# ST-Link_V2_Dongle.net
KiCad netlist of a schematic drawn in Altium Designer
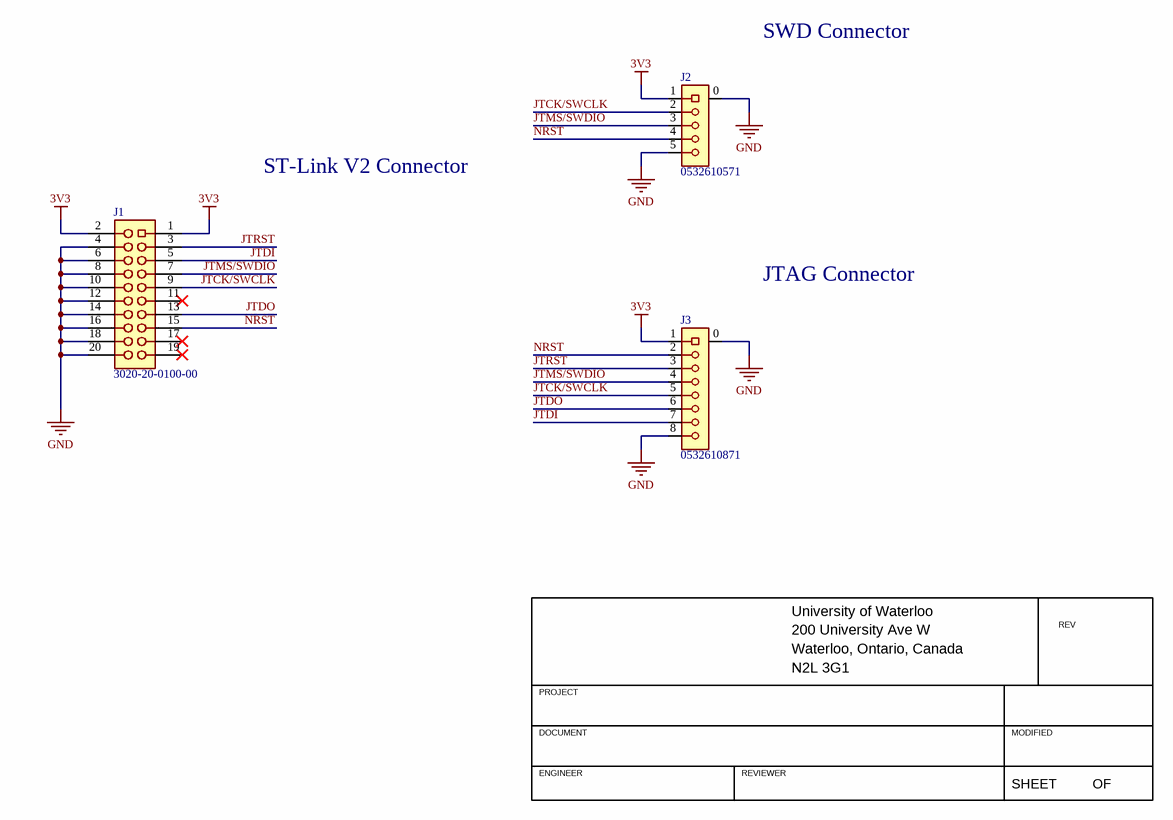
[diagram p0: ST-Link V2 Dongle.SchDoc]

(export (version "E")
  (design (tool "Eeschema 10.0.6"))
  (components
    (comp (ref "J1")
      (value "3020-20-0100-00")
      (footprint "CNC_3020-20-0100-00")
      (description "CONN HEADER VERT 20POS 2.54MM")
      (libsource (lib "Personal_Schematic_Library_2022") (part "CON_10x2_HEADER"))
    )
    (comp (ref "J2")
      (value "CON_MOLEX-PICO_5POS_RA")
      (footprint "MOLEX-532610571")
      (description "CONN HEADER SMD R/A 5POS 1.25MM")
      (fields (field (name "MANUFACTURER PART NUMBER 1") "0532610571"))
      (libsource (lib "Personal_Schematic_Library_2022") (part "CON_MOLEX-PICO_5POS_RA"))
    )
    (comp (ref "J3")
      (value "CON_MOLEX-PICO_8POS_RA")
      (footprint "MOLEX-532610871")
      (description "CONN HEADER SMD R/A 8POS 1.25MM")
      (fields (field (name "MANUFACTURER PART NUMBER 1") "0532610871"))
      (libsource (lib "Personal_Schematic_Library_2022") (part "CON_MOLEX-PICO_8POS_RA"))
    )
  )
  (nets
    (net (code "1") (name "/JTCK{slash}SWCLK") (class "Default")
      (node (ref "J1") (pin "9") (pinfunction "9_9") (pintype "passive"))
      (node (ref "J2") (pin "2") (pinfunction "2_2") (pintype "passive"))
      (node (ref "J3") (pin "5") (pinfunction "5_5") (pintype "passive"))
    )
    (net (code "2") (name "/JTDI") (class "Default")
      (node (ref "J1") (pin "5") (pinfunction "5_5") (pintype "passive"))
      (node (ref "J3") (pin "7") (pinfunction "7_7") (pintype "passive"))
    )
    (net (code "3") (name "/JTDO") (class "Default")
      (node (ref "J1") (pin "13") (pinfunction "13_13") (pintype "passive"))
      (node (ref "J3") (pin "6") (pinfunction "6_6") (pintype "passive"))
    )
    (net (code "4") (name "/JTMS{slash}SWDIO") (class "Default")
      (node (ref "J1") (pin "7") (pinfunction "7_7") (pintype "passive"))
      (node (ref "J2") (pin "3") (pinfunction "3_3") (pintype "passive"))
      (node (ref "J3") (pin "4") (pinfunction "4_4") (pintype "passive"))
    )
    (net (code "5") (name "/JTRST") (class "Default")
      (node (ref "J1") (pin "3") (pinfunction "3_3") (pintype "passive"))
      (node (ref "J3") (pin "3") (pinfunction "3_3") (pintype "passive"))
    )
    (net (code "6") (name "/NRST") (class "Default")
      (node (ref "J1") (pin "15") (pinfunction "15_15") (pintype "passive"))
      (node (ref "J2") (pin "4") (pinfunction "4_4") (pintype "passive"))
      (node (ref "J3") (pin "2") (pinfunction "2_2") (pintype "passive"))
    )
    (net (code "7") (name "3V3") (class "Default")
      (node (ref "J1") (pin "1") (pinfunction "1_1") (pintype "passive"))
      (node (ref "J1") (pin "2") (pinfunction "2_2") (pintype "passive"))
      (node (ref "J2") (pin "1") (pinfunction "1_1") (pintype "passive"))
      (node (ref "J3") (pin "1") (pinfunction "1_1") (pintype "passive"))
    )
    (net (code "8") (name "GND") (class "Default")
      (node (ref "J1") (pin "10") (pinfunction "10_10") (pintype "passive"))
      (node (ref "J1") (pin "12") (pinfunction "12_12") (pintype "passive"))
      (node (ref "J1") (pin "14") (pinfunction "14_14") (pintype "passive"))
      (node (ref "J1") (pin "16") (pinfunction "16_16") (pintype "passive"))
      (node (ref "J1") (pin "18") (pinfunction "18_18") (pintype "passive"))
      (node (ref "J1") (pin "20") (pinfunction "20_20") (pintype "passive"))
      (node (ref "J1") (pin "4") (pinfunction "4_4") (pintype "passive"))
      (node (ref "J1") (pin "6") (pinfunction "6_6") (pintype "passive"))
      (node (ref "J1") (pin "8") (pinfunction "8_8") (pintype "passive"))
      (node (ref "J2") (pin "0") (pinfunction "0_0") (pintype "passive"))
      (node (ref "J2") (pin "5") (pinfunction "5_5") (pintype "passive"))
      (node (ref "J3") (pin "0") (pinfunction "0_0") (pintype "passive"))
      (node (ref "J3") (pin "8") (pinfunction "8_8") (pintype "passive"))
    )
    (net (code "9") (name "unconnected-(J1-Pad11)") (class "Default")
      (node (ref "J1") (pin "11") (pinfunction "11_11") (pintype "passive+no_connect"))
    )
    (net (code "10") (name "unconnected-(J1-Pad17)") (class "Default")
      (node (ref "J1") (pin "17") (pinfunction "17_17") (pintype "passive+no_connect"))
    )
    (net (code "11") (name "unconnected-(J1-Pad19)") (class "Default")
      (node (ref "J1") (pin "19") (pinfunction "19_19") (pintype "passive+no_connect"))
    )
  )
)
